# Sche_Gas.net
KiCad netlist of a schematic drawn in EAGLE
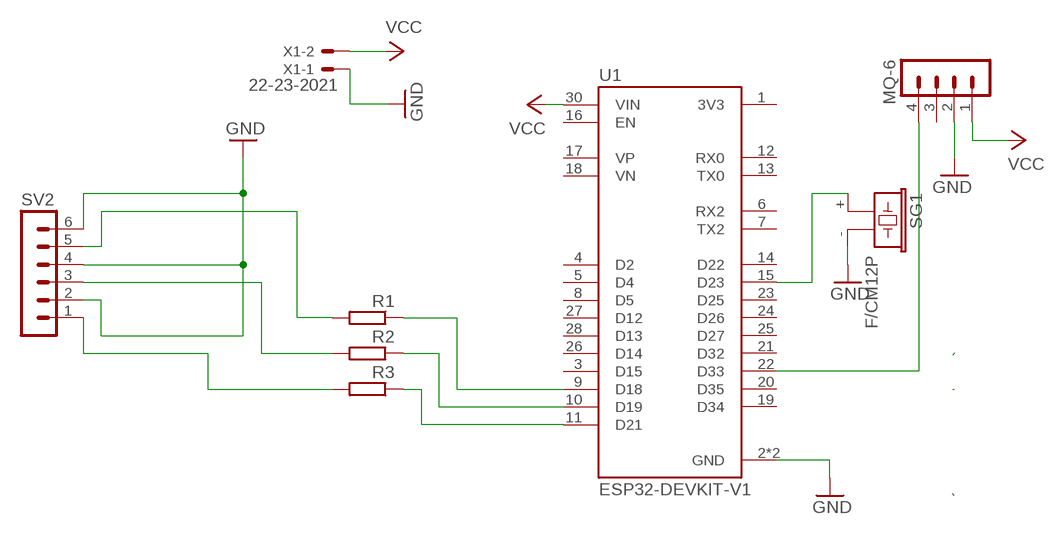
[diagram p0: schematic, sheet 1]

(export (version "E")
  (design (tool "Eeschema 10.0.6"))
  (components
    (comp (ref "MQ-6")
      (value "MA04-1")
      (footprint "eagle-import:MA04-1")
      (libsource (lib "eagle-import") (part "MA04-1"))
    )
    (comp (ref "R1")
      (value "R-EU_0204/7")
      (footprint "eagle-import:0204_7")
      (libsource (lib "eagle-import") (part "R-EU_0204/7"))
    )
    (comp (ref "R2")
      (value "R-EU_0204/7")
      (footprint "eagle-import:0204_7")
      (libsource (lib "eagle-import") (part "R-EU_0204/7"))
    )
    (comp (ref "R3")
      (value "R-EU_0204/7")
      (footprint "eagle-import:0204_7")
      (libsource (lib "eagle-import") (part "R-EU_0204/7"))
    )
    (comp (ref "SG1")
      (value "F/CM12P")
      (footprint "eagle-import:F_CM12P")
      (libsource (lib "eagle-import") (part "F/CM12P"))
    )
    (comp (ref "SV2")
      (value "MA06-1")
      (footprint "eagle-import:MA06-1")
      (libsource (lib "eagle-import") (part "MA06-1"))
    )
    (comp (ref "U1")
      (value "ESP32-DEVKIT-V1")
      (footprint "eagle-import:MODULE_ESP32_DEVKIT_V1")
      (fields (field (name "MF") "Do it"))
      (libsource (lib "eagle-import") (part "ESP32-DEVKIT-V1"))
    )
    (comp (ref "X1")
      (value "22-23-2021")
      (footprint "eagle-import:22-23-2021")
      (fields (field (name "MF") "MOLEX"))
      (libsource (lib "eagle-import") (part "22-23-2021"))
    )
  )
  (nets
    (net (code "1") (name "GND") (class "Default")
      (node (ref "MQ-6") (pin "2") (pinfunction "2_2") (pintype "passive"))
      (node (ref "SG1") (pin "-") (pinfunction "2_-") (pintype "passive"))
      (node (ref "SV2") (pin "2") (pinfunction "2_2") (pintype "passive"))
      (node (ref "SV2") (pin "4") (pinfunction "4_4") (pintype "passive"))
      (node (ref "SV2") (pin "6") (pinfunction "6_6") (pintype "passive"))
      (node (ref "U1") (pin "2") (pinfunction "GND_2") (pintype "power_in"))
      (node (ref "U1") (pin "29") (pinfunction "GND_29") (pintype "power_in"))
      (node (ref "X1") (pin "1") (pinfunction "S_1") (pintype "passive"))
    )
    (net (code "2") (name "Net-(R1-Pad2)") (class "Default")
      (node (ref "R1") (pin "2") (pinfunction "2_2") (pintype "passive"))
      (node (ref "SV2") (pin "5") (pinfunction "5_5") (pintype "passive"))
    )
    (net (code "3") (name "Net-(R2-Pad2)") (class "Default")
      (node (ref "R2") (pin "2") (pinfunction "2_2") (pintype "passive"))
      (node (ref "SV2") (pin "3") (pinfunction "3_3") (pintype "passive"))
    )
    (net (code "4") (name "Net-(R3-Pad2)") (class "Default")
      (node (ref "R3") (pin "2") (pinfunction "2_2") (pintype "passive"))
      (node (ref "SV2") (pin "1") (pinfunction "1_1") (pintype "passive"))
    )
    (net (code "5") (name "Net-(SG1-1)") (class "Default")
      (node (ref "SG1") (pin "+") (pinfunction "1_+") (pintype "passive"))
      (node (ref "U1") (pin "15") (pinfunction "D23_15") (pintype "bidirectional"))
    )
    (net (code "6") (name "Net-(U1-D18)") (class "Default")
      (node (ref "R1") (pin "1") (pinfunction "1_1") (pintype "passive"))
      (node (ref "U1") (pin "9") (pinfunction "D18_9") (pintype "bidirectional"))
    )
    (net (code "7") (name "Net-(U1-D19)") (class "Default")
      (node (ref "R2") (pin "1") (pinfunction "1_1") (pintype "passive"))
      (node (ref "U1") (pin "10") (pinfunction "D19_10") (pintype "bidirectional"))
    )
    (net (code "8") (name "Net-(U1-D21)") (class "Default")
      (node (ref "R3") (pin "1") (pinfunction "1_1") (pintype "passive"))
      (node (ref "U1") (pin "11") (pinfunction "D21_11") (pintype "bidirectional"))
    )
    (net (code "9") (name "Net-(U1-D33)") (class "Default")
      (node (ref "MQ-6") (pin "4") (pinfunction "4_4") (pintype "passive"))
      (node (ref "U1") (pin "22") (pinfunction "D33_22") (pintype "bidirectional"))
    )
    (net (code "10") (name "VCC") (class "Default")
      (node (ref "MQ-6") (pin "1") (pinfunction "1_1") (pintype "passive"))
      (node (ref "U1") (pin "30") (pinfunction "VIN_30") (pintype "input"))
      (node (ref "X1") (pin "2") (pinfunction "S_2") (pintype "passive"))
    )
    (net (code "11") (name "unconnected-(MQ-6-Pad3)") (class "Default")
      (node (ref "MQ-6") (pin "3") (pinfunction "3_3") (pintype "passive"))
    )
    (net (code "12") (name "unconnected-(U1-3V3-Pad1)") (class "Default")
      (node (ref "U1") (pin "1") (pinfunction "3V3_1") (pintype "output"))
    )
    (net (code "13") (name "unconnected-(U1-D2-Pad4)") (class "Default")
      (node (ref "U1") (pin "4") (pinfunction "D2_4") (pintype "bidirectional"))
    )
    (net (code "14") (name "unconnected-(U1-D4-Pad5)") (class "Default")
      (node (ref "U1") (pin "5") (pinfunction "D4_5") (pintype "bidirectional"))
    )
    (net (code "15") (name "unconnected-(U1-D5-Pad8)") (class "Default")
      (node (ref "U1") (pin "8") (pinfunction "D5_8") (pintype "bidirectional"))
    )
    (net (code "16") (name "unconnected-(U1-D12-Pad27)") (class "Default")
      (node (ref "U1") (pin "27") (pinfunction "D12_27") (pintype "bidirectional"))
    )
    (net (code "17") (name "unconnected-(U1-D13-Pad28)") (class "Default")
      (node (ref "U1") (pin "28") (pinfunction "D13_28") (pintype "bidirectional"))
    )
    (net (code "18") (name "unconnected-(U1-D14-Pad26)") (class "Default")
      (node (ref "U1") (pin "26") (pinfunction "D14_26") (pintype "bidirectional"))
    )
    (net (code "19") (name "unconnected-(U1-D15-Pad3)") (class "Default")
      (node (ref "U1") (pin "3") (pinfunction "D15_3") (pintype "bidirectional"))
    )
    (net (code "20") (name "unconnected-(U1-D22-Pad14)") (class "Default")
      (node (ref "U1") (pin "14") (pinfunction "D22_14") (pintype "bidirectional"))
    )
    (net (code "21") (name "unconnected-(U1-D25-Pad23)") (class "Default")
      (node (ref "U1") (pin "23") (pinfunction "D25_23") (pintype "bidirectional"))
    )
    (net (code "22") (name "unconnected-(U1-D26-Pad24)") (class "Default")
      (node (ref "U1") (pin "24") (pinfunction "D26_24") (pintype "bidirectional"))
    )
    (net (code "23") (name "unconnected-(U1-D27-Pad25)") (class "Default")
      (node (ref "U1") (pin "25") (pinfunction "D27_25") (pintype "bidirectional"))
    )
    (net (code "24") (name "unconnected-(U1-D32-Pad21)") (class "Default")
      (node (ref "U1") (pin "21") (pinfunction "D32_21") (pintype "bidirectional"))
    )
    (net (code "25") (name "unconnected-(U1-D34-Pad19)") (class "Default")
      (node (ref "U1") (pin "19") (pinfunction "D34_19") (pintype "bidirectional"))
    )
    (net (code "26") (name "unconnected-(U1-D35-Pad20)") (class "Default")
      (node (ref "U1") (pin "20") (pinfunction "D35_20") (pintype "bidirectional"))
    )
    (net (code "27") (name "unconnected-(U1-EN-Pad16)") (class "Default")
      (node (ref "U1") (pin "16") (pinfunction "EN_16") (pintype "input"))
    )
    (net (code "28") (name "unconnected-(U1-RX0-Pad12)") (class "Default")
      (node (ref "U1") (pin "12") (pinfunction "RX0_12") (pintype "input"))
    )
    (net (code "29") (name "unconnected-(U1-RX2-Pad6)") (class "Default")
      (node (ref "U1") (pin "6") (pinfunction "RX2_6") (pintype "input"))
    )
    (net (code "30") (name "unconnected-(U1-TX0-Pad13)") (class "Default")
      (node (ref "U1") (pin "13") (pinfunction "TX0_13") (pintype "output"))
    )
    (net (code "31") (name "unconnected-(U1-TX2-Pad7)") (class "Default")
      (node (ref "U1") (pin "7") (pinfunction "TX2_7") (pintype "output"))
    )
    (net (code "32") (name "unconnected-(U1-VN-Pad18)") (class "Default")
      (node (ref "U1") (pin "18") (pinfunction "VN_18") (pintype "bidirectional"))
    )
    (net (code "33") (name "unconnected-(U1-VP-Pad17)") (class "Default")
      (node (ref "U1") (pin "17") (pinfunction "VP_17") (pintype "bidirectional"))
    )
  )
)
